# ExpansionMain.net
KiCad netlist of a schematic drawn in Altium Designer
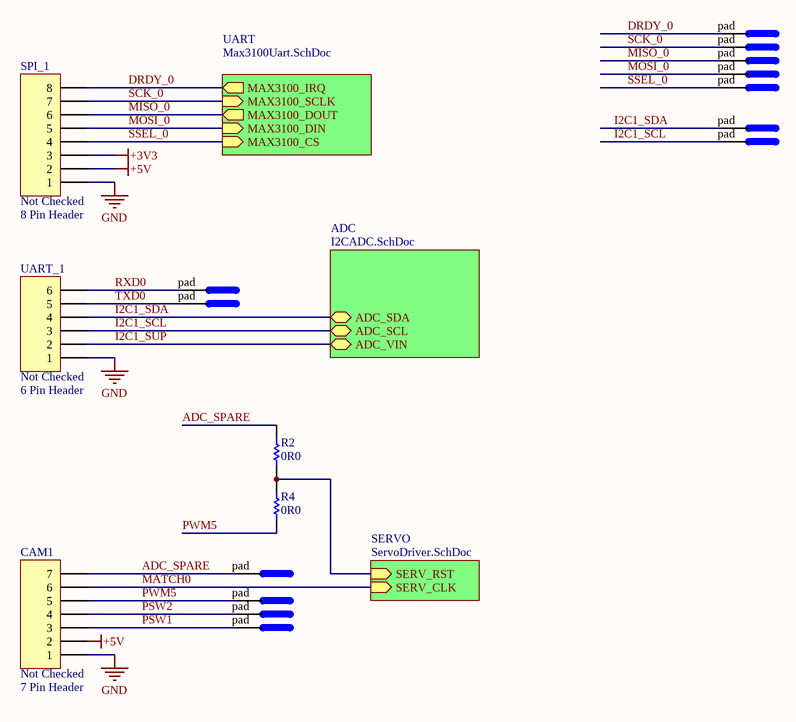
[diagram p0: ExpansionMain.SchDoc]

(export (version "E")
  (design (tool "Eeschema 10.0.6"))
  (components
    (comp (ref "A0")
      (value "~")
      (footprint "PAD_ROUND")
      (description "Pad")
      (libsource (lib "GRC sch library") (part "JP_pad"))
    )
    (comp (ref "CAM1")
      (value "7 Pin Header")
      (footprint "CONN_7X1_SMT_RA_1.25MM")
      (description "CONN HDR VERT 7POS .100\" SNGL")
      (fields (field (name "MANUFACTURER") "Molex") (field (name "VERIFY") "Not Checked"))
      (libsource (lib "GRC sch library") (part "JP_7PIN HDR_SMT_RA_MOLEX"))
    )
    (comp (ref "DRDY")
      (value "~")
      (footprint "PAD_ROUND")
      (description "Pad")
      (libsource (lib "GRC sch library") (part "JP_pad"))
    )
    (comp (ref "MISO")
      (value "~")
      (footprint "PAD_ROUND")
      (description "Pad")
      (libsource (lib "GRC sch library") (part "JP_pad"))
    )
    (comp (ref "MOSI")
      (value "~")
      (footprint "PAD_ROUND")
      (description "Pad")
      (libsource (lib "GRC sch library") (part "JP_pad"))
    )
    (comp (ref "PWM")
      (value "~")
      (footprint "PAD_ROUND")
      (description "Pad")
      (libsource (lib "GRC sch library") (part "JP_pad"))
    )
    (comp (ref "R2")
      (value "0R0")
      (footprint "0805")
      (description "RES 0.0 OHM 1/10W 5% 0603 SMD")
      (fields (field (name "MANUFACTURER") "Rohm"))
      (libsource (lib "GRC sch library") (part "RS_0R0 0603"))
    )
    (comp (ref "R4")
      (value "0R0")
      (footprint "0805")
      (description "RES 0.0 OHM 1/10W 5% 0603 SMD")
      (fields (field (name "MANUFACTURER") "Rohm"))
      (libsource (lib "GRC sch library") (part "RS_0R0 0603"))
    )
    (comp (ref "RX0")
      (value "~")
      (footprint "PAD_ROUND")
      (description "Pad")
      (libsource (lib "") (part "JP_pad_1"))
    )
    (comp (ref "SCK")
      (value "~")
      (footprint "PAD_ROUND")
      (description "Pad")
      (libsource (lib "GRC sch library") (part "JP_pad"))
    )
    (comp (ref "SCL")
      (value "~")
      (footprint "PAD_ROUND")
      (description "Pad")
      (libsource (lib "GRC sch library") (part "JP_pad"))
    )
    (comp (ref "SDA")
      (value "~")
      (footprint "PAD_ROUND")
      (description "Pad")
      (libsource (lib "GRC sch library") (part "JP_pad"))
    )
    (comp (ref "SPI_1")
      (value "8 Pin Header")
      (footprint "CONN_8X1_SMT_RA_1.25MM")
      (description "CONN HDR VERT 12POS .100\" SNGL")
      (fields (field (name "MANUFACTURER") "Molex") (field (name "VERIFY") "Not Checked"))
      (libsource (lib "GRC sch library") (part "JP_8PIN HDR_SMT_RA_MOLEX"))
    )
    (comp (ref "SSEL")
      (value "~")
      (footprint "PAD_ROUND")
      (description "Pad")
      (libsource (lib "GRC sch library") (part "JP_pad"))
    )
    (comp (ref "SW1")
      (value "~")
      (footprint "PAD_ROUND")
      (description "Pad")
      (libsource (lib "") (part "JP_pad_1"))
    )
    (comp (ref "SW2")
      (value "~")
      (footprint "PAD_ROUND")
      (description "Pad")
      (libsource (lib "") (part "JP_pad_1"))
    )
    (comp (ref "TX0")
      (value "~")
      (footprint "PAD_ROUND")
      (description "Pad")
      (libsource (lib "") (part "JP_pad_1"))
    )
    (comp (ref "UART_1")
      (value "6 Pin Header")
      (footprint "CONN_6X1_SMT_RA_1.25MM")
      (description "CONN HDR VERT 6POS .100\" SNGL")
      (fields (field (name "MANUFACTURER") "Molex") (field (name "VERIFY") "Not Checked"))
      (libsource (lib "GRC sch library") (part "JP_6PIN HDR_SMT_RA_MOLEX"))
    )
  )
  (nets
    (net (code "1") (name "+3V3") (class "Default")
      (node (ref "SPI_1") (pin "3") (pinfunction "3_3") (pintype "passive"))
    )
    (net (code "2") (name "+5V") (class "Default")
      (node (ref "CAM1") (pin "2") (pinfunction "2_2") (pintype "passive"))
      (node (ref "SPI_1") (pin "2") (pinfunction "2_2") (pintype "passive"))
    )
    (net (code "3") (name "/ADC_SPARE") (class "Default")
      (node (ref "A0") (pin "pad") (pintype "passive"))
      (node (ref "CAM1") (pin "7") (pinfunction "7_7") (pintype "passive"))
      (node (ref "R2") (pin "1") (pinfunction "1_1") (pintype "passive"))
    )
    (net (code "4") (name "/DRDY_0") (class "Default")
      (node (ref "DRDY") (pin "pad") (pintype "passive"))
      (node (ref "SPI_1") (pin "8") (pinfunction "8_8") (pintype "passive"))
    )
    (net (code "5") (name "/I2C1_SCL") (class "Default")
      (node (ref "SCL") (pin "pad") (pintype "passive"))
      (node (ref "UART_1") (pin "3") (pinfunction "3_3") (pintype "passive"))
    )
    (net (code "6") (name "/I2C1_SDA") (class "Default")
      (node (ref "SDA") (pin "pad") (pintype "passive"))
      (node (ref "UART_1") (pin "4") (pinfunction "4_4") (pintype "passive"))
    )
    (net (code "7") (name "/I2C1_SUP") (class "Default")
      (node (ref "UART_1") (pin "2") (pinfunction "2_2") (pintype "passive"))
    )
    (net (code "8") (name "/MATCH0") (class "Default")
      (node (ref "CAM1") (pin "6") (pinfunction "6_6") (pintype "passive"))
    )
    (net (code "9") (name "/MISO_0") (class "Default")
      (node (ref "MISO") (pin "pad") (pintype "passive"))
      (node (ref "SPI_1") (pin "6") (pinfunction "6_6") (pintype "passive"))
    )
    (net (code "10") (name "/MOSI_0") (class "Default")
      (node (ref "MOSI") (pin "pad") (pintype "passive"))
      (node (ref "SPI_1") (pin "5") (pinfunction "5_5") (pintype "passive"))
    )
    (net (code "11") (name "/PSW1") (class "Default")
      (node (ref "CAM1") (pin "3") (pinfunction "3_3") (pintype "passive"))
      (node (ref "SW1") (pin "pad") (pintype "passive"))
    )
    (net (code "12") (name "/PSW2") (class "Default")
      (node (ref "CAM1") (pin "4") (pinfunction "4_4") (pintype "passive"))
      (node (ref "SW2") (pin "pad") (pintype "passive"))
    )
    (net (code "13") (name "/PWM5") (class "Default")
      (node (ref "CAM1") (pin "5") (pinfunction "5_5") (pintype "passive"))
      (node (ref "PWM") (pin "pad") (pintype "passive"))
      (node (ref "R4") (pin "2") (pinfunction "2_2") (pintype "passive"))
    )
    (net (code "14") (name "/RXD0") (class "Default")
      (node (ref "RX0") (pin "pad") (pintype "passive"))
      (node (ref "UART_1") (pin "6") (pinfunction "6_6") (pintype "passive"))
    )
    (net (code "15") (name "/SCK_0") (class "Default")
      (node (ref "SCK") (pin "pad") (pintype "passive"))
      (node (ref "SPI_1") (pin "7") (pinfunction "7_7") (pintype "passive"))
    )
    (net (code "16") (name "/SERV_RST") (class "Default")
      (node (ref "R2") (pin "2") (pinfunction "2_2") (pintype "passive"))
      (node (ref "R4") (pin "1") (pinfunction "1_1") (pintype "passive"))
    )
    (net (code "17") (name "/SSEL_0") (class "Default")
      (node (ref "SPI_1") (pin "4") (pinfunction "4_4") (pintype "passive"))
      (node (ref "SSEL") (pin "pad") (pintype "passive"))
    )
    (net (code "18") (name "/TXD0") (class "Default")
      (node (ref "TX0") (pin "pad") (pintype "passive"))
      (node (ref "UART_1") (pin "5") (pinfunction "5_5") (pintype "passive"))
    )
    (net (code "19") (name "GND") (class "Default")
      (node (ref "CAM1") (pin "1") (pinfunction "1_1") (pintype "passive"))
      (node (ref "SPI_1") (pin "1") (pinfunction "1_1") (pintype "passive"))
      (node (ref "UART_1") (pin "1") (pinfunction "1_1") (pintype "passive"))
    )
  )
)
